# 5_-_Motor_Driver_Schematic.net
KiCad netlist of a schematic drawn in Altium Designer
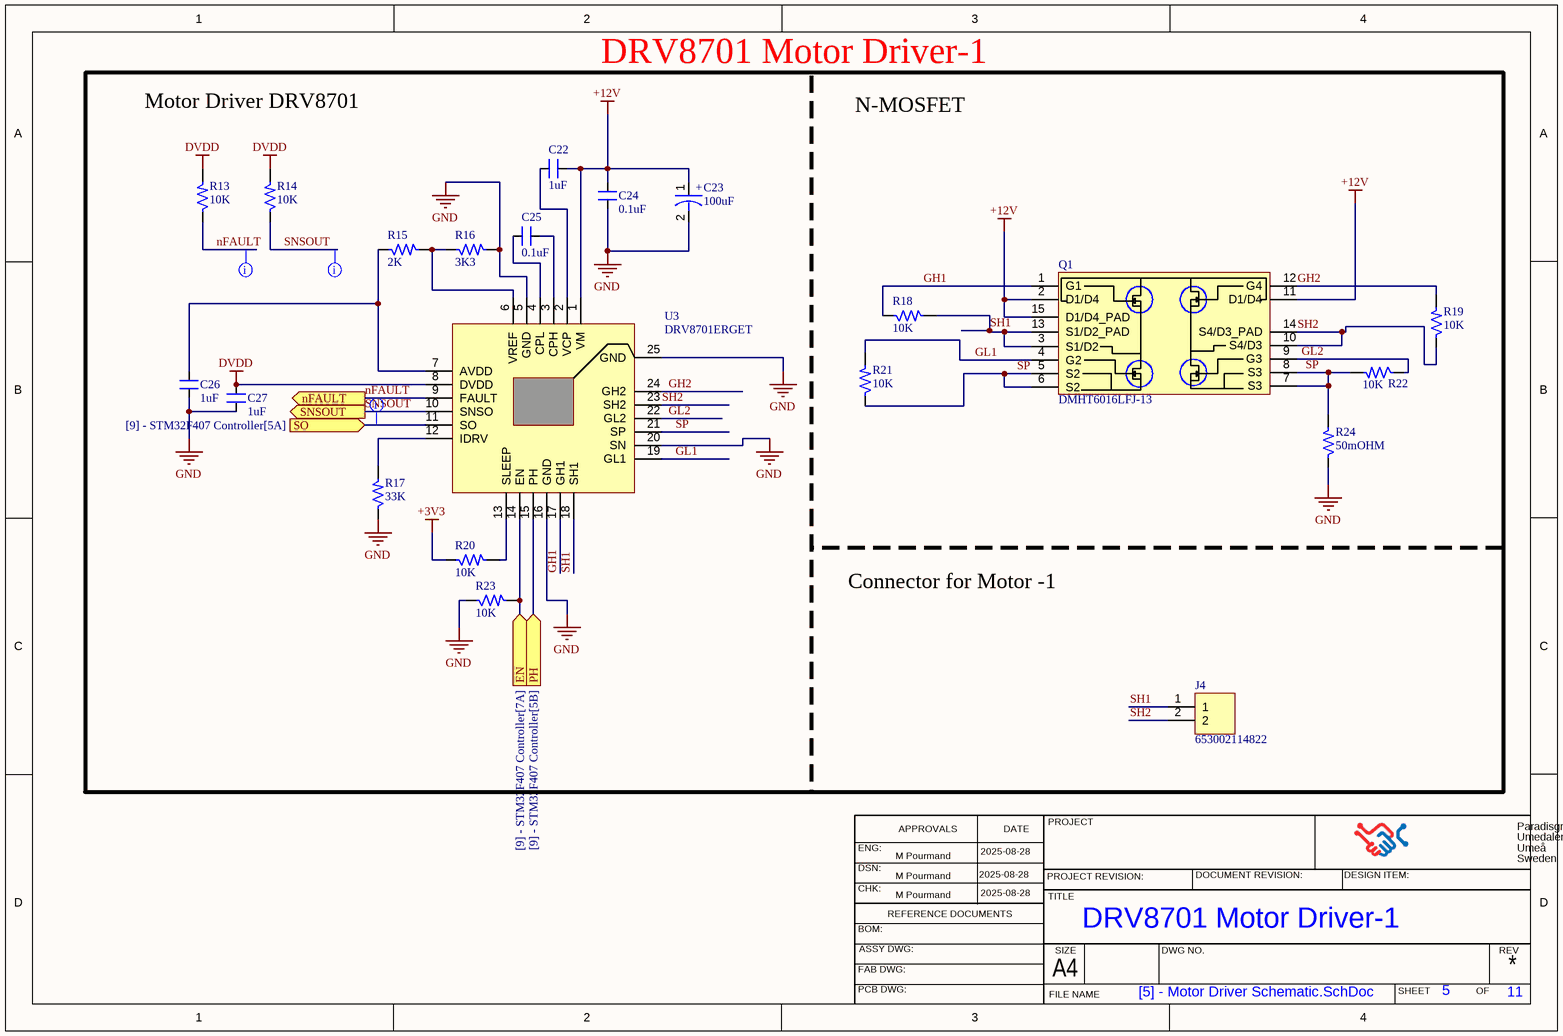
[diagram p0: [5] - Motor Driver Schematic.SchDoc]

(export (version "E")
  (design (tool "Eeschema 10.0.6"))
  (components
    (comp (ref "C22")
      (value "1uF")
      (footprint "CAP_0805")
      (description "1µF ±5% 50V Ceramic Capacitor X7R 0805 (2012 Metric)")
      (fields
        (field (name "MANUFACTURER") "Samsung")
        (field (name "MANUFACTURER PART NUMBER") "CC0805JKX7R9BB105")
      )
      (libsource (lib "ESTEEMPCBLIB") (part "CAP_1uF-50V-5%-0805"))
    )
    (comp (ref "C23")
      (value "100uF")
      (footprint "ACAP_P236_D305_H303_RAD")
      (description "100µF 25V Aluminum Electrolytic Capacitors Radial, Can - SMD 1000 Hrs @ 105°C")
      (fields
        (field (name "MANUFACTURER") "Nichicon")
        (field (name "MANUFACTURER PART NUMBER") "UWT1E101MCL1GS")
      )
      (libsource (lib "ESTEEMPCBLIB") (part "CAP-P_100uF-25V-20%-RAD"))
    )
    (comp (ref "C24")
      (value "0.1uF")
      (footprint "CAP_0805")
      (description "0.1µF ±10% 50V Ceramic Capacitor X7R 0805 (2012 Metric)")
      (fields
        (field (name "MANUFACTURER") "Samsung")
        (field (name "MANUFACTURER PART NUMBER") "CL21B104KBCNNNC")
      )
      (libsource (lib "ESTEEMPCBLIB") (part "CAP_0.1uF-50V-10%-0805"))
    )
    (comp (ref "C25")
      (value "0.1uF")
      (footprint "CAP_0805")
      (description "0.1µF ±10% 50V Ceramic Capacitor X7R 0805 (2012 Metric)")
      (fields
        (field (name "MANUFACTURER") "Samsung")
        (field (name "MANUFACTURER PART NUMBER") "CL21B104KBCNNNC")
      )
      (libsource (lib "ESTEEMPCBLIB") (part "CAP_0.1uF-50V-10%-0805"))
    )
    (comp (ref "C26")
      (value "1uF")
      (footprint "CAP_0805")
      (description "1µF ±5% 50V Ceramic Capacitor X7R 0805 (2012 Metric)")
      (fields
        (field (name "MANUFACTURER") "Samsung")
        (field (name "MANUFACTURER PART NUMBER") "CC0805JKX7R9BB105")
      )
      (libsource (lib "ESTEEMPCBLIB") (part "CAP_1uF-50V-5%-0805"))
    )
    (comp (ref "C27")
      (value "1uF")
      (footprint "CAP_0805")
      (description "1µF ±5% 50V Ceramic Capacitor X7R 0805 (2012 Metric)")
      (fields
        (field (name "MANUFACTURER") "Samsung")
        (field (name "MANUFACTURER PART NUMBER") "CC0805JKX7R9BB105")
      )
      (libsource (lib "ESTEEMPCBLIB") (part "CAP_1uF-50V-5%-0805"))
    )
    (comp (ref "J4")
      (value "653002114822")
      (footprint "CON2_50_653002114822_TH_ST")
      (description "2 Pins, 1 Row 1.25mm Pitch, Straight Connector, male")
      (fields (field (name "MANUFACTURER") "JST") (field (name "MATING PART NUMBER") "653002113322"))
      (libsource (lib "ESTEEMPCBLIB") (part "CON-PLG_2X1-50-ST-TH"))
    )
    (comp (ref "Q1")
      (value "DMHT6016LFJ-13")
      (footprint "DFN5045-12_33_212_27X15_SMD_1")
      (description "Mosfet Array 4 N-Channel 14.8A (Ta) Surface Mount V-DFN5045-12")
      (fields (field (name "MANUFACTURER") "ON Semiconductor"))
      (libsource (lib "ESTEEMPCBLIB") (part "MOSFET-N_60V-14.8A-V-DFN5045-12"))
    )
    (comp (ref "R13")
      (value "10K")
      (footprint "RES_0603")
      (description "10 kOhms ±1% 0.1W, 1/10W Chip Resistor 0603 (1608 Metric) Automotive AEC-Q200 Thick Film")
      (fields (field (name "MANUFACTURER") "Walsin") (field (name "MANUFACTURER PART NUMBER") "WR06X1002FTL"))
      (libsource (lib "ESTEEMPCBLIB") (part "RES_10K-0.1W-1%-0603"))
    )
    (comp (ref "R14")
      (value "10K")
      (footprint "RES_0603")
      (description "10 kOhms ±1% 0.1W, 1/10W Chip Resistor 0603 (1608 Metric) Automotive AEC-Q200 Thick Film")
      (fields (field (name "MANUFACTURER") "Walsin") (field (name "MANUFACTURER PART NUMBER") "WR06X1002FTL"))
      (libsource (lib "ESTEEMPCBLIB") (part "RES_10K-0.1W-1%-0603"))
    )
    (comp (ref "R15")
      (value "2K")
      (footprint "RES_0603")
      (fields
        (field (name "MANUFACTURER") "Stackpole Electronics")
        (field (name "MANUFACTURER PART NUMBER") "RNCP0603FTD2K00")
      )
      (libsource (lib "ESTEEMPCBLIB") (part "RES_2K-0.125W-1%-0603"))
    )
    (comp (ref "R16")
      (value "3K3")
      (footprint "RES_0603")
      (description "3.3 kOhms ±1% 0.1W, 1/10W Chip Resistor 0603 (1608 Metric) Automotive AEC-Q200 Thick Film")
      (fields (field (name "MANUFACTURER") "Wilson") (field (name "MANUFACTURER PART NUMBER") "WR06X3301FTL"))
      (libsource (lib "ESTEEMPCBLIB") (part "RES_3.3K-0.1W-1%-0603"))
    )
    (comp (ref "R17")
      (value "33K")
      (footprint "RES_0805")
      (fields
        (field (name "MANUFACTURER") "Vishay BCcomponents")
        (field (name "MANUFACTURER PART NUMBER") "CRG0805F33K")
      )
      (libsource (lib "ESTEEMPCBLIB") (part "RES_33K-0.125W-1%-0805"))
    )
    (comp (ref "R18")
      (value "10K")
      (footprint "RES_0603")
      (description "10 kOhms ±1% 0.1W, 1/10W Chip Resistor 0603 (1608 Metric) Automotive AEC-Q200 Thick Film")
      (fields (field (name "MANUFACTURER") "Walsin") (field (name "MANUFACTURER PART NUMBER") "WR06X1002FTL"))
      (libsource (lib "ESTEEMPCBLIB") (part "RES_10K-0.1W-1%-0603"))
    )
    (comp (ref "R19")
      (value "10K")
      (footprint "RES_0603")
      (description "10 kOhms ±1% 0.1W, 1/10W Chip Resistor 0603 (1608 Metric) Automotive AEC-Q200 Thick Film")
      (fields (field (name "MANUFACTURER") "Walsin") (field (name "MANUFACTURER PART NUMBER") "WR06X1002FTL"))
      (libsource (lib "ESTEEMPCBLIB") (part "RES_10K-0.1W-1%-0603"))
    )
    (comp (ref "R20")
      (value "10K")
      (footprint "RES_0603")
      (description "10 kOhms ±1% 0.1W, 1/10W Chip Resistor 0603 (1608 Metric) Automotive AEC-Q200 Thick Film")
      (fields (field (name "MANUFACTURER") "Walsin") (field (name "MANUFACTURER PART NUMBER") "WR06X1002FTL"))
      (libsource (lib "ESTEEMPCBLIB") (part "RES_10K-0.1W-1%-0603"))
    )
    (comp (ref "R21")
      (value "10K")
      (footprint "RES_0603")
      (description "10 kOhms ±1% 0.1W, 1/10W Chip Resistor 0603 (1608 Metric) Automotive AEC-Q200 Thick Film")
      (fields (field (name "MANUFACTURER") "Walsin") (field (name "MANUFACTURER PART NUMBER") "WR06X1002FTL"))
      (libsource (lib "ESTEEMPCBLIB") (part "RES_10K-0.1W-1%-0603"))
    )
    (comp (ref "R22")
      (value "10K")
      (footprint "RES_0603")
      (description "10 kOhms ±1% 0.1W, 1/10W Chip Resistor 0603 (1608 Metric) Automotive AEC-Q200 Thick Film")
      (fields (field (name "MANUFACTURER") "Walsin") (field (name "MANUFACTURER PART NUMBER") "WR06X1002FTL"))
      (libsource (lib "ESTEEMPCBLIB") (part "RES_10K-0.1W-1%-0603"))
    )
    (comp (ref "R23")
      (value "10K")
      (footprint "RES_0603")
      (description "10 kOhms ±1% 0.1W, 1/10W Chip Resistor 0603 (1608 Metric) Automotive AEC-Q200 Thick Film")
      (fields (field (name "MANUFACTURER") "Walsin") (field (name "MANUFACTURER PART NUMBER") "WR06X1002FTL"))
      (libsource (lib "ESTEEMPCBLIB") (part "RES_10K-0.1W-1%-0603"))
    )
    (comp (ref "R24")
      (value "50mOHM")
      (footprint "RES_2512")
      (fields
        (field (name "MANUFACTURER") "Yageo")
        (field (name "MANUFACTURER PART NUMBER") "PA2512FKF7W0R05E")
      )
      (libsource (lib "ESTEEMPCBLIB") (part "RES_50mOhm-2W-1%-2512"))
    )
    (comp (ref "U3")
      (value "DRV8701ERGET")
      (footprint "VFQFN24_19.6_196_12X32_SMD_1")
      (description "Motor Driver Power MOSFET Parallel 24-VQFN (4x4)")
      (fields (field (name "MANUFACTURER") "Texas Instruments"))
      (libsource (lib "ESTEEMPCBLIB") (part "IC_DRV8701ERGET"))
    )
  )
  (nets
    (net (code "1") (name "+3V3") (class "Default")
      (node (ref "R20") (pin "1") (pinfunction "1_1") (pintype "passive"))
    )
    (net (code "2") (name "+12V") (class "Default")
      (node (ref "C22") (pin "2") (pinfunction "2_2") (pintype "passive"))
      (node (ref "C23") (pin "1") (pinfunction "1_1") (pintype "passive"))
      (node (ref "C24") (pin "2") (pinfunction "2_2") (pintype "passive"))
      (node (ref "Q1") (pin "11") (pinfunction "D1/D4_11") (pintype "passive"))
      (node (ref "Q1") (pin "15") (pinfunction "D1/D4_PAD_15") (pintype "passive"))
      (node (ref "Q1") (pin "2") (pinfunction "D1/D4_2") (pintype "passive"))
      (node (ref "U3") (pin "1") (pinfunction "VM_1") (pintype "passive"))
    )
    (net (code "3") (name "/EN") (class "Default")
      (node (ref "R23") (pin "2") (pinfunction "2_2") (pintype "passive"))
      (node (ref "U3") (pin "14") (pinfunction "EN_14") (pintype "passive"))
    )
    (net (code "4") (name "/GH1") (class "Default")
      (node (ref "Q1") (pin "1") (pinfunction "G1_1") (pintype "passive"))
      (node (ref "R18") (pin "1") (pinfunction "1_1") (pintype "passive"))
      (node (ref "U3") (pin "17") (pinfunction "GH1_17") (pintype "passive"))
    )
    (net (code "5") (name "/GH2") (class "Default")
      (node (ref "Q1") (pin "12") (pinfunction "G4_12") (pintype "passive"))
      (node (ref "R19") (pin "2") (pinfunction "2_2") (pintype "passive"))
      (node (ref "U3") (pin "24") (pinfunction "GH2_24") (pintype "passive"))
    )
    (net (code "6") (name "/GL1") (class "Default")
      (node (ref "Q1") (pin "4") (pinfunction "G2_4") (pintype "passive"))
      (node (ref "R21") (pin "2") (pinfunction "2_2") (pintype "passive"))
      (node (ref "U3") (pin "19") (pinfunction "GL1_19") (pintype "passive"))
    )
    (net (code "7") (name "/GL2") (class "Default")
      (node (ref "Q1") (pin "9") (pinfunction "G3_9") (pintype "passive"))
      (node (ref "R22") (pin "1") (pinfunction "1_1") (pintype "passive"))
      (node (ref "U3") (pin "22") (pinfunction "GL2_22") (pintype "passive"))
    )
    (net (code "8") (name "/PH") (class "Default")
      (node (ref "U3") (pin "15") (pinfunction "PH_15") (pintype "passive"))
    )
    (net (code "9") (name "/SH1") (class "Default")
      (node (ref "J4") (pin "1") (pinfunction "1_1") (pintype "passive"))
      (node (ref "Q1") (pin "13") (pinfunction "S1/D2_PAD_13") (pintype "passive"))
      (node (ref "Q1") (pin "3") (pinfunction "S1/D2_3") (pintype "passive"))
      (node (ref "R18") (pin "2") (pinfunction "2_2") (pintype "passive"))
      (node (ref "U3") (pin "18") (pinfunction "SH1_18") (pintype "passive"))
    )
    (net (code "10") (name "/SH2") (class "Default")
      (node (ref "J4") (pin "2") (pinfunction "2_2") (pintype "passive"))
      (node (ref "Q1") (pin "10") (pinfunction "S4/D3_10") (pintype "passive"))
      (node (ref "Q1") (pin "14") (pinfunction "S4/D3_PAD_14") (pintype "passive"))
      (node (ref "R19") (pin "1") (pinfunction "1_1") (pintype "passive"))
      (node (ref "U3") (pin "23") (pinfunction "SH2_23") (pintype "passive"))
    )
    (net (code "11") (name "/SNSOUT") (class "Default")
      (node (ref "R14") (pin "1") (pinfunction "1_1") (pintype "passive"))
      (node (ref "U3") (pin "10") (pinfunction "SNSO_10") (pintype "passive"))
    )
    (net (code "12") (name "/SO") (class "Default")
      (node (ref "U3") (pin "11") (pinfunction "SO_11") (pintype "passive"))
    )
    (net (code "13") (name "/SP") (class "Default")
      (node (ref "Q1") (pin "5") (pinfunction "S2_5") (pintype "passive"))
      (node (ref "Q1") (pin "6") (pinfunction "S2_6") (pintype "passive"))
      (node (ref "Q1") (pin "7") (pinfunction "S3_7") (pintype "passive"))
      (node (ref "Q1") (pin "8") (pinfunction "S3_8") (pintype "passive"))
      (node (ref "R21") (pin "1") (pinfunction "1_1") (pintype "passive"))
      (node (ref "R22") (pin "2") (pinfunction "2_2") (pintype "passive"))
      (node (ref "R24") (pin "2") (pinfunction "2_2") (pintype "passive"))
      (node (ref "U3") (pin "21") (pinfunction "SP_21") (pintype "passive"))
    )
    (net (code "14") (name "/nFAULT") (class "Default")
      (node (ref "R13") (pin "1") (pinfunction "1_1") (pintype "passive"))
      (node (ref "U3") (pin "9") (pinfunction "FAULT_9") (pintype "passive"))
    )
    (net (code "15") (name "DVDD") (class "Default")
      (node (ref "C27") (pin "2") (pinfunction "2_2") (pintype "passive"))
      (node (ref "R13") (pin "2") (pinfunction "2_2") (pintype "passive"))
      (node (ref "R14") (pin "2") (pinfunction "2_2") (pintype "passive"))
      (node (ref "U3") (pin "8") (pinfunction "DVDD_8") (pintype "passive"))
    )
    (net (code "16") (name "GND") (class "Default")
      (node (ref "C23") (pin "2") (pinfunction "2_2") (pintype "passive"))
      (node (ref "C24") (pin "1") (pinfunction "1_1") (pintype "passive"))
      (node (ref "C26") (pin "1") (pinfunction "1_1") (pintype "passive"))
      (node (ref "C27") (pin "1") (pinfunction "1_1") (pintype "passive"))
      (node (ref "R16") (pin "2") (pinfunction "2_2") (pintype "passive"))
      (node (ref "R17") (pin "1") (pinfunction "1_1") (pintype "passive"))
      (node (ref "R23") (pin "1") (pinfunction "1_1") (pintype "passive"))
      (node (ref "R24") (pin "1") (pinfunction "1_1") (pintype "passive"))
      (node (ref "U3") (pin "16") (pinfunction "GND_16") (pintype "passive"))
      (node (ref "U3") (pin "20") (pinfunction "SN_20") (pintype "passive"))
      (node (ref "U3") (pin "25") (pinfunction "GND_25") (pintype "passive"))
      (node (ref "U3") (pin "5") (pinfunction "GND_5") (pintype "passive"))
    )
    (net (code "17") (name "Net-(U3-AVDD)") (class "Default")
      (node (ref "C26") (pin "2") (pinfunction "2_2") (pintype "passive"))
      (node (ref "R15") (pin "1") (pinfunction "1_1") (pintype "passive"))
      (node (ref "U3") (pin "7") (pinfunction "AVDD_7") (pintype "passive"))
    )
    (net (code "18") (name "Net-(U3-CPH)") (class "Default")
      (node (ref "C25") (pin "1") (pinfunction "1_1") (pintype "passive"))
      (node (ref "U3") (pin "3") (pinfunction "CPH_3") (pintype "passive"))
    )
    (net (code "19") (name "Net-(U3-CPL)") (class "Default")
      (node (ref "C25") (pin "2") (pinfunction "2_2") (pintype "passive"))
      (node (ref "U3") (pin "4") (pinfunction "CPL_4") (pintype "passive"))
    )
    (net (code "20") (name "Net-(U3-IDRV)") (class "Default")
      (node (ref "R17") (pin "2") (pinfunction "2_2") (pintype "passive"))
      (node (ref "U3") (pin "12") (pinfunction "IDRV_12") (pintype "passive"))
    )
    (net (code "21") (name "Net-(U3-SLEEP)") (class "Default")
      (node (ref "R20") (pin "2") (pinfunction "2_2") (pintype "passive"))
      (node (ref "U3") (pin "13") (pinfunction "SLEEP_13") (pintype "passive"))
    )
    (net (code "22") (name "Net-(U3-VCP)") (class "Default")
      (node (ref "C22") (pin "1") (pinfunction "1_1") (pintype "passive"))
      (node (ref "U3") (pin "2") (pinfunction "VCP_2") (pintype "passive"))
    )
    (net (code "23") (name "Net-(U3-VREF)") (class "Default")
      (node (ref "R15") (pin "2") (pinfunction "2_2") (pintype "passive"))
      (node (ref "R16") (pin "1") (pinfunction "1_1") (pintype "passive"))
      (node (ref "U3") (pin "6") (pinfunction "VREF_6") (pintype "passive"))
    )
  )
)
